# untitled.net
KiCad netlist of a schematic drawn in EAGLE
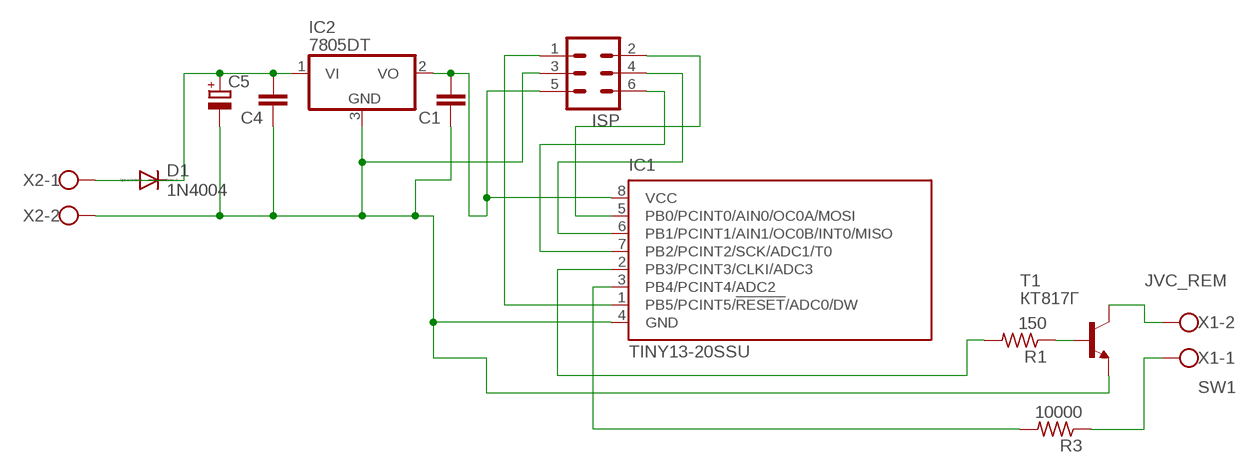
[diagram p0: schematic, sheet 1]

(export (version "E")
  (design (tool "Eeschema 10.0.6"))
  (components
    (comp (ref "C1")
      (value "C2.5/2")
      (footprint "eagle-import:C2.5-2")
      (libsource (lib "eagle-import") (part "C2.5/2"))
    )
    (comp (ref "C4")
      (value "C2.5/2")
      (footprint "eagle-import:C2.5-2")
      (libsource (lib "eagle-import") (part "C2.5/2"))
    )
    (comp (ref "C5")
      (value "CPOL-EUE5-10.5")
      (footprint "eagle-import:E5-10,5")
      (libsource (lib "eagle-import") (part "CPOL-EUE5-10.5"))
    )
    (comp (ref "D1")
      (value "1N4004")
      (footprint "eagle-import:DO41-10")
      (libsource (lib "eagle-import") (part "1N4004"))
    )
    (comp (ref "IC1")
      (value "TINY13-20SSU")
      (footprint "eagle-import:8S1")
      (fields (field (name "MPN") "ATTINY13-20SSU"))
      (libsource (lib "eagle-import") (part "TINY13SSU-20"))
    )
    (comp (ref "IC2")
      (value "7805DT")
      (footprint "eagle-import:TO252")
      (libsource (lib "eagle-import") (part "78DT05"))
    )
    (comp (ref "ISP")
      (value "MA03-2")
      (footprint "eagle-import:MA03-2")
      (libsource (lib "eagle-import") (part "MA03-2"))
    )
    (comp (ref "R1")
      (value "150")
      (footprint "eagle-import:M1206")
      (libsource (lib "eagle-import") (part "R-US_M1206"))
    )
    (comp (ref "R3")
      (value "10000")
      (footprint "eagle-import:M1206")
      (libsource (lib "eagle-import") (part "R-US_M1206"))
    )
    (comp (ref "T1")
      (value "КТ817Г")
      (footprint "eagle-import:TO220AV")
      (libsource (lib "eagle-import") (part "2SC1307"))
    )
    (comp (ref "X1")
      (value "W237-102")
      (footprint "eagle-import:W237-102")
      (fields (field (name "MPN") "237-102"))
      (libsource (lib "eagle-import") (part "W237-102"))
    )
    (comp (ref "X2")
      (value "W237-102")
      (footprint "eagle-import:W237-102")
      (fields (field (name "MPN") "237-102"))
      (libsource (lib "eagle-import") (part "W237-102"))
    )
  )
  (nets
    (net (code "1") (name "/JVC_REM") (class "Default")
      (node (ref "T1") (pin "2") (pinfunction "C_2") (pintype "passive"))
      (node (ref "X1") (pin "2") (pinfunction "KL_2") (pintype "passive"))
    )
    (net (code "2") (name "/SW1") (class "Default")
      (node (ref "R3") (pin "1") (pinfunction "1_1") (pintype "passive"))
      (node (ref "X1") (pin "1") (pinfunction "KL_1") (pintype "passive"))
    )
    (net (code "3") (name "Net-(IC1-GND)") (class "Default")
      (node (ref "C1") (pin "1") (pinfunction "1_1") (pintype "passive"))
      (node (ref "C4") (pin "1") (pinfunction "1_1") (pintype "passive"))
      (node (ref "C5") (pin "-") (pinfunction "-_-") (pintype "passive"))
      (node (ref "IC1") (pin "4") (pinfunction "GND_4") (pintype "power_in"))
      (node (ref "IC2") (pin "3") (pinfunction "GND_3") (pintype "passive"))
      (node (ref "ISP") (pin "3") (pinfunction "3_3") (pintype "passive"))
      (node (ref "T1") (pin "3") (pinfunction "E_3") (pintype "passive"))
      (node (ref "X2") (pin "2") (pinfunction "KL_2") (pintype "passive"))
    )
    (net (code "4") (name "Net-(IC1-PB0{slash}PCINT0{slash}AIN0{slash}OC0A{slash}MOSI)") (class "Default")
      (node (ref "IC1") (pin "5") (pinfunction "PB0/PCINT0/AIN0/OC0A/MOSI_5") (pintype "bidirectional"))
      (node (ref "ISP") (pin "2") (pinfunction "2_2") (pintype "passive"))
    )
    (net (code "5") (name "Net-(IC1-PB1{slash}PCINT1{slash}AIN1{slash}OC0B{slash}INT0{slash}MISO)") (class "Default")
      (node (ref "IC1") (pin "6") (pinfunction "PB1/PCINT1/AIN1/OC0B/INT0/MISO_6") (pintype "bidirectional"))
      (node (ref "ISP") (pin "4") (pinfunction "4_4") (pintype "passive"))
    )
    (net (code "6") (name "Net-(IC1-PB2{slash}PCINT2{slash}SCK{slash}ADC1{slash}T0)") (class "Default")
      (node (ref "IC1") (pin "7") (pinfunction "PB2/PCINT2/SCK/ADC1/T0_7") (pintype "bidirectional"))
      (node (ref "ISP") (pin "6") (pinfunction "6_6") (pintype "passive"))
    )
    (net (code "7") (name "Net-(IC1-PB3{slash}PCINT3{slash}CLKI{slash}ADC3)") (class "Default")
      (node (ref "IC1") (pin "2") (pinfunction "PB3/PCINT3/CLKI/ADC3_2") (pintype "bidirectional"))
      (node (ref "R1") (pin "2") (pinfunction "2_2") (pintype "passive"))
    )
    (net (code "8") (name "Net-(IC1-PB4{slash}PCINT4{slash}ADC2)") (class "Default")
      (node (ref "IC1") (pin "3") (pinfunction "PB4/PCINT4/ADC2_3") (pintype "bidirectional"))
      (node (ref "R3") (pin "2") (pinfunction "2_2") (pintype "passive"))
    )
    (net (code "9") (name "Net-(IC1-PB5{slash}PCINT5{slash}~{RESET}{slash}ADC0{slash}DW)") (class "Default")
      (node (ref "IC1") (pin "1") (pinfunction "PB5/PCINT5/~{RESET}/ADC0/DW_1") (pintype "bidirectional"))
      (node (ref "ISP") (pin "1") (pinfunction "1_1") (pintype "passive"))
    )
    (net (code "10") (name "Net-(IC1-VCC)") (class "Default")
      (node (ref "C1") (pin "2") (pinfunction "2_2") (pintype "passive"))
      (node (ref "IC1") (pin "8") (pinfunction "VCC_8") (pintype "power_in"))
      (node (ref "IC2") (pin "2") (pinfunction "VO_2") (pintype "passive"))
      (node (ref "ISP") (pin "5") (pinfunction "5_5") (pintype "passive"))
    )
    (net (code "11") (name "Net-(IC2-VI)") (class "Default")
      (node (ref "C4") (pin "2") (pinfunction "2_2") (pintype "passive"))
      (node (ref "C5") (pin "+") (pinfunction "+_+") (pintype "passive"))
      (node (ref "D1") (pin "A") (pinfunction "A_A") (pintype "passive"))
      (node (ref "IC2") (pin "1") (pinfunction "VI_1") (pintype "input"))
    )
    (net (code "12") (name "Net-(T1-B)") (class "Default")
      (node (ref "R1") (pin "1") (pinfunction "1_1") (pintype "passive"))
      (node (ref "T1") (pin "1") (pinfunction "B_1") (pintype "passive"))
    )
    (net (code "13") (name "Net-(X2A-KL)") (class "Default")
      (node (ref "D1") (pin "C") (pinfunction "C_C") (pintype "passive"))
      (node (ref "X2") (pin "1") (pinfunction "KL_1") (pintype "passive"))
    )
  )
)
